# Sheet1.net
KiCad netlist of a schematic drawn in Altium Designer
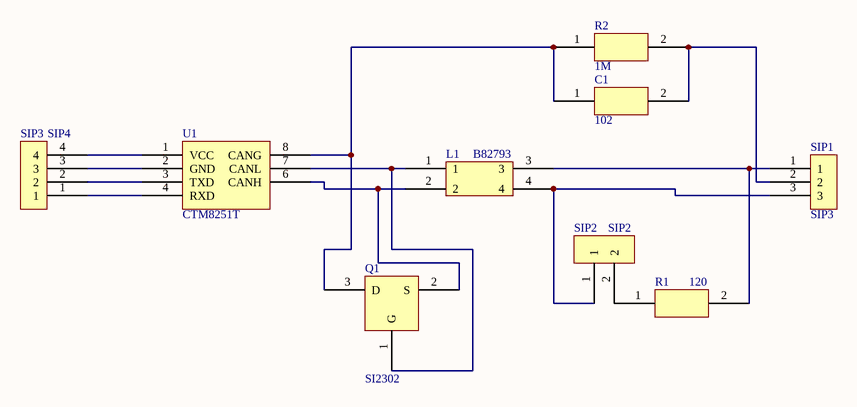
[diagram p0: Sheet1.SchDoc]

(export (version "E")
  (design (tool "Eeschema 10.0.6"))
  (components
    (comp (ref "C1") (value "102") (footprint "RES-T") (libsource (lib "qudong") (part "RES-T")))
    (comp (ref "L1") (value "B82793") (footprint "B82793") (libsource (lib "qudong") (part "B82793")))
    (comp (ref "Q1") (value "SI2302") (footprint "SI2302") (libsource (lib "qudong") (part "SI2302")))
    (comp (ref "R1") (value "120") (footprint "RES-T") (libsource (lib "qudong") (part "RES-T")))
    (comp (ref "R2") (value "1M") (footprint "RES-T") (libsource (lib "qudong") (part "RES-T")))
    (comp (ref "SIP1") (value "SIP3") (footprint "SIP3") (libsource (lib "qudong") (part "SIP3")))
    (comp (ref "SIP2") (value "SIP2") (footprint "SIP2") (libsource (lib "qudong") (part "SIP2")))
    (comp (ref "SIP3") (value "SIP4") (footprint "SIP4") (libsource (lib "qudong") (part "SIP4")))
    (comp (ref "U1") (value "CTM8251T") (footprint "CTM8251T") (libsource (lib "qudong") (part "CTM8251T")))
  )
  (nets
    (net (code "1") (name "Net-(C1-Pad2)") (class "Default")
      (node (ref "C1") (pin "2") (pinfunction "2_2") (pintype "passive"))
      (node (ref "R2") (pin "2") (pinfunction "2_2") (pintype "passive"))
      (node (ref "SIP1") (pin "2") (pinfunction "2_2") (pintype "passive"))
    )
    (net (code "2") (name "Net-(L1-Pad3)") (class "Default")
      (node (ref "L1") (pin "3") (pinfunction "3_3") (pintype "passive"))
      (node (ref "R1") (pin "2") (pinfunction "2_2") (pintype "passive"))
      (node (ref "SIP1") (pin "1") (pinfunction "1_1") (pintype "passive"))
    )
    (net (code "3") (name "Net-(L1-Pad4)") (class "Default")
      (node (ref "L1") (pin "4") (pinfunction "4_4") (pintype "passive"))
      (node (ref "SIP1") (pin "3") (pinfunction "3_3") (pintype "passive"))
      (node (ref "SIP2") (pin "1") (pinfunction "1_1") (pintype "passive"))
    )
    (net (code "4") (name "Net-(Q1-D)") (class "Default")
      (node (ref "C1") (pin "1") (pinfunction "1_1") (pintype "passive"))
      (node (ref "Q1") (pin "3") (pinfunction "D_3") (pintype "passive"))
      (node (ref "R2") (pin "1") (pinfunction "1_1") (pintype "passive"))
      (node (ref "U1") (pin "8") (pinfunction "CANG_8") (pintype "passive"))
    )
    (net (code "5") (name "Net-(Q1-G)") (class "Default")
      (node (ref "L1") (pin "1") (pinfunction "1_1") (pintype "passive"))
      (node (ref "Q1") (pin "1") (pinfunction "G_1") (pintype "passive"))
      (node (ref "U1") (pin "7") (pinfunction "CANL_7") (pintype "passive"))
    )
    (net (code "6") (name "Net-(Q1-S)") (class "Default")
      (node (ref "L1") (pin "2") (pinfunction "2_2") (pintype "passive"))
      (node (ref "Q1") (pin "2") (pinfunction "S_2") (pintype "passive"))
      (node (ref "U1") (pin "6") (pinfunction "CANH_6") (pintype "passive"))
    )
    (net (code "7") (name "Net-(R1-Pad1)") (class "Default")
      (node (ref "R1") (pin "1") (pinfunction "1_1") (pintype "passive"))
      (node (ref "SIP2") (pin "2") (pinfunction "2_2") (pintype "passive"))
    )
    (net (code "8") (name "Net-(U1-GND)") (class "Default")
      (node (ref "SIP3") (pin "3") (pinfunction "3_3") (pintype "passive"))
      (node (ref "U1") (pin "2") (pinfunction "GND_2") (pintype "passive"))
    )
    (net (code "9") (name "Net-(U1-RXD)") (class "Default")
      (node (ref "SIP3") (pin "1") (pinfunction "1_1") (pintype "passive"))
      (node (ref "U1") (pin "4") (pinfunction "RXD_4") (pintype "passive"))
    )
    (net (code "10") (name "Net-(U1-TXD)") (class "Default")
      (node (ref "SIP3") (pin "2") (pinfunction "2_2") (pintype "passive"))
      (node (ref "U1") (pin "3") (pinfunction "TXD_3") (pintype "passive"))
    )
    (net (code "11") (name "Net-(U1-VCC)") (class "Default")
      (node (ref "SIP3") (pin "4") (pinfunction "4_4") (pintype "passive"))
      (node (ref "U1") (pin "1") (pinfunction "VCC_1") (pintype "passive"))
    )
  )
)
